# mini.net
KiCad netlist of a schematic drawn in EAGLE
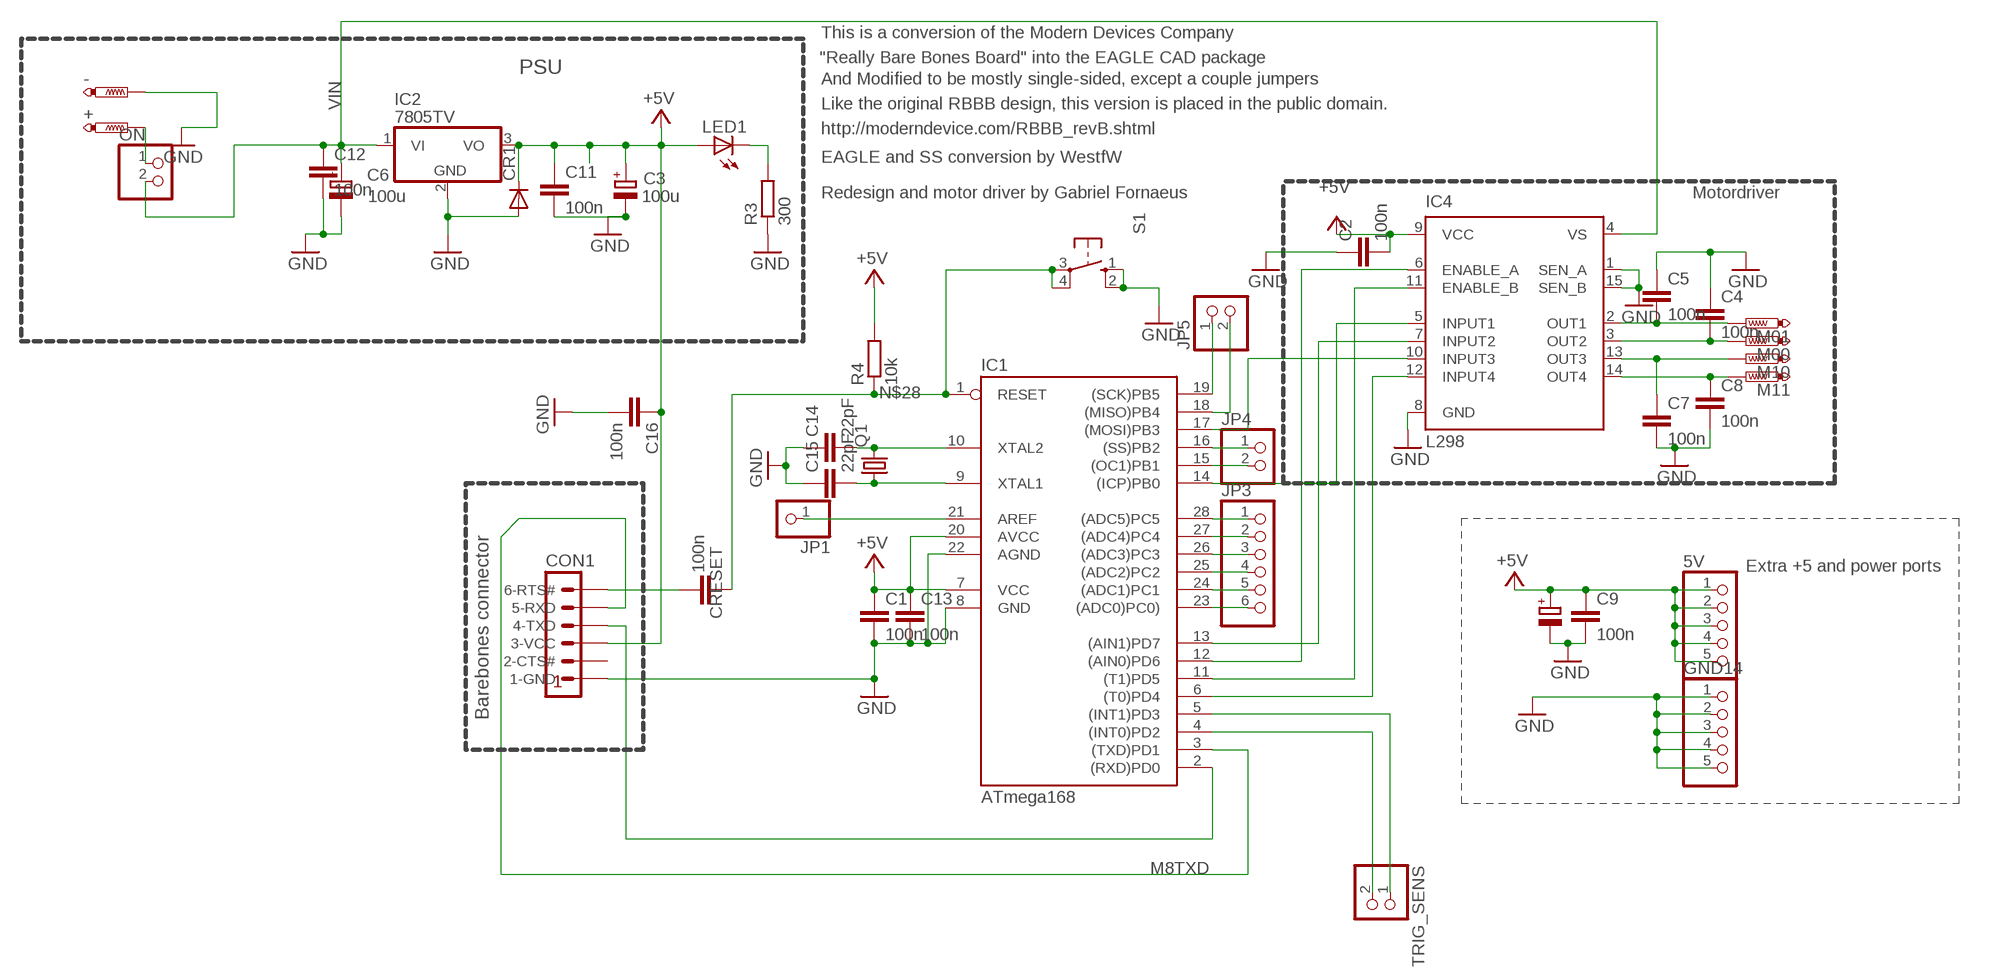
[diagram p0: schematic, sheet 1]

(export (version "E")
  (design (tool "Eeschema 10.0.6"))
  (components
    (comp (ref "+")
      (value "PTR1PAD1-13Y")
      (footprint "eagle-import:P1-13Y")
      (libsource (lib "eagle-import") (part "PTR1PAD1-13Y"))
    )
    (comp (ref "-")
      (value "PTR1PAD1-13Y")
      (footprint "eagle-import:P1-13Y")
      (libsource (lib "eagle-import") (part "PTR1PAD1-13Y"))
    )
    (comp (ref "5V")
      (value "PINHD-1X5")
      (footprint "eagle-import:1X05")
      (libsource (lib "eagle-import") (part "PINHD-1X5"))
    )
    (comp (ref "C1")
      (value "100n")
      (footprint "eagle-import:C025-025X050")
      (libsource (lib "eagle-import") (part "C-EU025-025X050"))
    )
    (comp (ref "C2")
      (value "100n")
      (footprint "eagle-import:C025-025X050")
      (libsource (lib "eagle-import") (part "C-EU025-025X050"))
    )
    (comp (ref "C3")
      (value "100u")
      (footprint "eagle-import:E2,5-7")
      (libsource (lib "eagle-import") (part "CPOL-EUE2.5-7"))
    )
    (comp (ref "C4")
      (value "100n")
      (footprint "eagle-import:C025-025X050")
      (libsource (lib "eagle-import") (part "C-EU025-025X050"))
    )
    (comp (ref "C5")
      (value "100n")
      (footprint "eagle-import:C025-025X050")
      (libsource (lib "eagle-import") (part "C-EU025-025X050"))
    )
    (comp (ref "C6")
      (value "100u")
      (footprint "eagle-import:E2,5-7")
      (libsource (lib "eagle-import") (part "CPOL-EUE2.5-7"))
    )
    (comp (ref "C7")
      (value "100n")
      (footprint "eagle-import:C025-025X050")
      (libsource (lib "eagle-import") (part "C-EU025-025X050"))
    )
    (comp (ref "C8")
      (value "100n")
      (footprint "eagle-import:C025-025X050")
      (libsource (lib "eagle-import") (part "C-EU025-025X050"))
    )
    (comp (ref "C9")
      (value "100n")
      (footprint "eagle-import:C025-025X050")
      (libsource (lib "eagle-import") (part "C-EU025-025X050"))
    )
    (comp (ref "C10")
      (value "100u")
      (footprint "eagle-import:E2,5-7")
      (libsource (lib "eagle-import") (part "CPOL-EUE2.5-7"))
    )
    (comp (ref "C11")
      (value "100n")
      (footprint "eagle-import:C025-025X050")
      (libsource (lib "eagle-import") (part "C-EU025-025X050"))
    )
    (comp (ref "C12")
      (value "100n")
      (footprint "eagle-import:C025-025X050")
      (libsource (lib "eagle-import") (part "C-EU025-025X050"))
    )
    (comp (ref "C13")
      (value "100n")
      (footprint "eagle-import:C025-025X050")
      (libsource (lib "eagle-import") (part "C-EU025-025X050"))
    )
    (comp (ref "C14")
      (value "22pF")
      (footprint "eagle-import:C025-024X044")
      (libsource (lib "eagle-import") (part "resistor_C-EU025-024X044"))
    )
    (comp (ref "C15")
      (value "22pF")
      (footprint "eagle-import:C025-024X044")
      (libsource (lib "eagle-import") (part "resistor_C-EU025-024X044"))
    )
    (comp (ref "C16")
      (value "100n")
      (footprint "eagle-import:C025-025X050")
      (libsource (lib "eagle-import") (part "C-EU025-025X050"))
    )
    (comp (ref "CON1")
      (value "FTDI-TTL232R")
      (footprint "eagle-import:MA06-1")
      (libsource (lib "eagle-import") (part "FTDI-TTL232R"))
    )
    (comp (ref "CR1")
      (value "DIODE-1ARECT-2V")
      (footprint "eagle-import:DO41-2V")
      (libsource (lib "eagle-import") (part "DIODE-1ARECT-2V"))
    )
    (comp (ref "CRESET")
      (value "100n")
      (footprint "eagle-import:C025-025X050")
      (libsource (lib "eagle-import") (part "C-EU025-025X050"))
    )
    (comp (ref "GND14")
      (value "PINHD-1X5")
      (footprint "eagle-import:1X05")
      (libsource (lib "eagle-import") (part "PINHD-1X5"))
    )
    (comp (ref "IC1")
      (value "ATmega168")
      (footprint "eagle-import:DIL28-3")
      (libsource (lib "eagle-import") (part "AT90S4433P"))
    )
    (comp (ref "IC2")
      (value "7805TV")
      (footprint "eagle-import:TO220V")
      (libsource (lib "eagle-import") (part "78TV05"))
    )
    (comp (ref "IC4")
      (value "L298")
      (footprint "eagle-import:MULTIWATT-15")
      (fields (field (name "MPN") "L298N"))
      (libsource (lib "eagle-import") (part "L298"))
    )
    (comp (ref "JP1")
      (value "PINHD-1X1")
      (footprint "eagle-import:1X01")
      (libsource (lib "eagle-import") (part "PINHD-1X1"))
    )
    (comp (ref "JP3")
      (value "PINHD-1X6")
      (footprint "eagle-import:1X06")
      (libsource (lib "eagle-import") (part "PINHD-1X6"))
    )
    (comp (ref "JP4")
      (value "PINHD-1X2")
      (footprint "eagle-import:1X02")
      (libsource (lib "eagle-import") (part "PINHD-1X2"))
    )
    (comp (ref "JP5")
      (value "PINHD-1X2")
      (footprint "eagle-import:1X02")
      (libsource (lib "eagle-import") (part "PINHD-1X2"))
    )
    (comp (ref "LED1")
      (value "LED3MM")
      (footprint "eagle-import:LED3MM")
      (libsource (lib "eagle-import") (part "LED3MM"))
    )
    (comp (ref "M00")
      (value "PTR1PAD1-13Y")
      (footprint "eagle-import:P1-13Y")
      (libsource (lib "eagle-import") (part "PTR1PAD1-13Y"))
    )
    (comp (ref "M01")
      (value "PTR1PAD1-13Y")
      (footprint "eagle-import:P1-13Y")
      (libsource (lib "eagle-import") (part "PTR1PAD1-13Y"))
    )
    (comp (ref "M10")
      (value "PTR1PAD1-13Y")
      (footprint "eagle-import:P1-13Y")
      (libsource (lib "eagle-import") (part "PTR1PAD1-13Y"))
    )
    (comp (ref "M11")
      (value "PTR1PAD1-13Y")
      (footprint "eagle-import:P1-13Y")
      (libsource (lib "eagle-import") (part "PTR1PAD1-13Y"))
    )
    (comp (ref "ON")
      (value "PINHD-1X2")
      (footprint "eagle-import:1X02")
      (libsource (lib "eagle-import") (part "PINHD-1X2"))
    )
    (comp (ref "Q1")
      (value "CRYSTALHC49S")
      (footprint "eagle-import:HC49_S")
      (libsource (lib "eagle-import") (part "CRYSTALHC49S"))
    )
    (comp (ref "R3")
      (value "300")
      (footprint "eagle-import:0204_7")
      (libsource (lib "eagle-import") (part "R-EU_0204/7"))
    )
    (comp (ref "R4")
      (value "10k")
      (footprint "eagle-import:0204_7")
      (libsource (lib "eagle-import") (part "R-EU_0204/7"))
    )
    (comp (ref "S1")
      (value "10-XX")
      (footprint "eagle-import:B3F-10XX")
      (libsource (lib "eagle-import") (part "10-XX"))
    )
    (comp (ref "TRIG_SENS")
      (value "PINHD-1X2")
      (footprint "eagle-import:1X02")
      (libsource (lib "eagle-import") (part "PINHD-1X2"))
    )
  )
  (nets
    (net (code "1") (name "+5V") (class "Default")
      (node (ref "5V") (pin "1") (pinfunction "1_1") (pintype "passive"))
      (node (ref "5V") (pin "2") (pinfunction "2_2") (pintype "passive"))
      (node (ref "5V") (pin "3") (pinfunction "3_3") (pintype "passive"))
      (node (ref "5V") (pin "4") (pinfunction "4_4") (pintype "passive"))
      (node (ref "5V") (pin "5") (pinfunction "5_5") (pintype "passive"))
      (node (ref "C1") (pin "1") (pinfunction "1_1") (pintype "passive"))
      (node (ref "C10") (pin "+") (pinfunction "+_+") (pintype "passive"))
      (node (ref "C11") (pin "1") (pinfunction "1_1") (pintype "passive"))
      (node (ref "C13") (pin "1") (pinfunction "1_1") (pintype "passive"))
      (node (ref "C16") (pin "1") (pinfunction "1_1") (pintype "passive"))
      (node (ref "C2") (pin "2") (pinfunction "2_2") (pintype "passive"))
      (node (ref "C3") (pin "+") (pinfunction "+_+") (pintype "passive"))
      (node (ref "C9") (pin "1") (pinfunction "1_1") (pintype "passive"))
      (node (ref "CON1") (pin "3") (pinfunction "3-VCC_3") (pintype "passive"))
      (node (ref "CR1") (pin "C") (pinfunction "C_C") (pintype "passive"))
      (node (ref "IC1") (pin "20") (pinfunction "AVCC_20") (pintype "power_in"))
      (node (ref "IC1") (pin "7") (pinfunction "VCC_7") (pintype "power_in"))
      (node (ref "IC2") (pin "3") (pinfunction "VO_3") (pintype "passive"))
      (node (ref "IC4") (pin "9") (pinfunction "VCC_9") (pintype "power_in"))
      (node (ref "LED1") (pin "A") (pinfunction "A_A") (pintype "passive"))
      (node (ref "R4") (pin "2") (pinfunction "2_2") (pintype "passive"))
    )
    (net (code "2") (name "/M8TXD") (class "Default")
      (node (ref "CON1") (pin "5") (pinfunction "5-RXD_5") (pintype "passive"))
      (node (ref "IC1") (pin "3") (pinfunction "(TXD)PD1_3") (pintype "bidirectional"))
    )
    (net (code "3") (name "/N$28") (class "Default")
      (node (ref "CRESET") (pin "2") (pinfunction "2_2") (pintype "passive"))
      (node (ref "IC1") (pin "1") (pinfunction "RESET_1") (pintype "input"))
      (node (ref "R4") (pin "1") (pinfunction "1_1") (pintype "passive"))
      (node (ref "S1") (pin "3") (pinfunction "P_3") (pintype "passive"))
      (node (ref "S1") (pin "4") (pinfunction "P1_4") (pintype "passive"))
    )
    (net (code "4") (name "/VIN") (class "Default")
      (node (ref "C12") (pin "1") (pinfunction "1_1") (pintype "passive"))
      (node (ref "C6") (pin "+") (pinfunction "+_+") (pintype "passive"))
      (node (ref "IC2") (pin "1") (pinfunction "VI_1") (pintype "input"))
      (node (ref "IC4") (pin "4") (pinfunction "VS_4") (pintype "power_in"))
      (node (ref "ON") (pin "2") (pinfunction "2_2") (pintype "passive"))
    )
    (net (code "5") (name "GND") (class "Default")
      (node (ref "-") (pin "TP") (pinfunction "TP_TP") (pintype "input"))
      (node (ref "C1") (pin "2") (pinfunction "2_2") (pintype "passive"))
      (node (ref "C10") (pin "-") (pinfunction "-_-") (pintype "passive"))
      (node (ref "C11") (pin "2") (pinfunction "2_2") (pintype "passive"))
      (node (ref "C12") (pin "2") (pinfunction "2_2") (pintype "passive"))
      (node (ref "C13") (pin "2") (pinfunction "2_2") (pintype "passive"))
      (node (ref "C14") (pin "1") (pinfunction "1_1") (pintype "passive"))
      (node (ref "C15") (pin "1") (pinfunction "1_1") (pintype "passive"))
      (node (ref "C16") (pin "2") (pinfunction "2_2") (pintype "passive"))
      (node (ref "C2") (pin "1") (pinfunction "1_1") (pintype "passive"))
      (node (ref "C3") (pin "-") (pinfunction "-_-") (pintype "passive"))
      (node (ref "C4") (pin "1") (pinfunction "1_1") (pintype "passive"))
      (node (ref "C5") (pin "1") (pinfunction "1_1") (pintype "passive"))
      (node (ref "C6") (pin "-") (pinfunction "-_-") (pintype "passive"))
      (node (ref "C7") (pin "2") (pinfunction "2_2") (pintype "passive"))
      (node (ref "C8") (pin "2") (pinfunction "2_2") (pintype "passive"))
      (node (ref "C9") (pin "2") (pinfunction "2_2") (pintype "passive"))
      (node (ref "CON1") (pin "1") (pinfunction "1-GND_1") (pintype "passive"))
      (node (ref "CR1") (pin "A") (pinfunction "A_A") (pintype "passive"))
      (node (ref "GND14") (pin "1") (pinfunction "1_1") (pintype "passive"))
      (node (ref "GND14") (pin "2") (pinfunction "2_2") (pintype "passive"))
      (node (ref "GND14") (pin "3") (pinfunction "3_3") (pintype "passive"))
      (node (ref "GND14") (pin "4") (pinfunction "4_4") (pintype "passive"))
      (node (ref "GND14") (pin "5") (pinfunction "5_5") (pintype "passive"))
      (node (ref "IC1") (pin "22") (pinfunction "AGND_22") (pintype "power_in"))
      (node (ref "IC1") (pin "8") (pinfunction "GND_8") (pintype "power_in"))
      (node (ref "IC2") (pin "2") (pinfunction "GND_2") (pintype "passive"))
      (node (ref "IC4") (pin "1") (pinfunction "SEN_A_1") (pintype "input"))
      (node (ref "IC4") (pin "15") (pinfunction "SEN_B_15") (pintype "input"))
      (node (ref "IC4") (pin "8") (pinfunction "GND_8") (pintype "power_in"))
      (node (ref "R3") (pin "1") (pinfunction "1_1") (pintype "passive"))
      (node (ref "S1") (pin "1") (pinfunction "S_1") (pintype "passive"))
      (node (ref "S1") (pin "2") (pinfunction "S1_2") (pintype "passive"))
    )
    (net (code "6") (name "Net-(+-PadTP)") (class "Default")
      (node (ref "+") (pin "TP") (pinfunction "TP_TP") (pintype "input"))
      (node (ref "ON") (pin "1") (pinfunction "1_1") (pintype "passive"))
    )
    (net (code "7") (name "Net-(CON1-4-TXD)") (class "Default")
      (node (ref "CON1") (pin "4") (pinfunction "4-TXD_4") (pintype "passive"))
      (node (ref "IC1") (pin "2") (pinfunction "(RXD)PD0_2") (pintype "bidirectional"))
    )
    (net (code "8") (name "Net-(CON1-6-RTS#)") (class "Default")
      (node (ref "CON1") (pin "6") (pinfunction "6-RTS#_6") (pintype "passive"))
      (node (ref "CRESET") (pin "1") (pinfunction "1_1") (pintype "passive"))
    )
    (net (code "9") (name "Net-(IC1-(ADC0)PC0))") (class "Default")
      (node (ref "IC1") (pin "23") (pinfunction "(ADC0)PC0)_23") (pintype "bidirectional"))
      (node (ref "JP3") (pin "6") (pinfunction "6_6") (pintype "passive"))
    )
    (net (code "10") (name "Net-(IC1-(ADC1)PC1)") (class "Default")
      (node (ref "IC1") (pin "24") (pinfunction "(ADC1)PC1_24") (pintype "bidirectional"))
      (node (ref "JP3") (pin "5") (pinfunction "5_5") (pintype "passive"))
    )
    (net (code "11") (name "Net-(IC1-(ADC2)PC2)") (class "Default")
      (node (ref "IC1") (pin "25") (pinfunction "(ADC2)PC2_25") (pintype "bidirectional"))
      (node (ref "JP3") (pin "4") (pinfunction "4_4") (pintype "passive"))
    )
    (net (code "12") (name "Net-(IC1-(ADC3)PC3)") (class "Default")
      (node (ref "IC1") (pin "26") (pinfunction "(ADC3)PC3_26") (pintype "bidirectional"))
      (node (ref "JP3") (pin "3") (pinfunction "3_3") (pintype "passive"))
    )
    (net (code "13") (name "Net-(IC1-(ADC4)PC4)") (class "Default")
      (node (ref "IC1") (pin "27") (pinfunction "(ADC4)PC4_27") (pintype "bidirectional"))
      (node (ref "JP3") (pin "2") (pinfunction "2_2") (pintype "passive"))
    )
    (net (code "14") (name "Net-(IC1-(ADC5)PC5)") (class "Default")
      (node (ref "IC1") (pin "28") (pinfunction "(ADC5)PC5_28") (pintype "bidirectional"))
      (node (ref "JP3") (pin "1") (pinfunction "1_1") (pintype "passive"))
    )
    (net (code "15") (name "Net-(IC1-(AIN0)PD6)") (class "Default")
      (node (ref "IC1") (pin "12") (pinfunction "(AIN0)PD6_12") (pintype "bidirectional"))
      (node (ref "IC4") (pin "6") (pinfunction "ENABLE_A_6") (pintype "input"))
    )
    (net (code "16") (name "Net-(IC1-(AIN1)PD7)") (class "Default")
      (node (ref "IC1") (pin "13") (pinfunction "(AIN1)PD7_13") (pintype "bidirectional"))
      (node (ref "IC4") (pin "7") (pinfunction "INPUT2_7") (pintype "input"))
    )
    (net (code "17") (name "Net-(IC1-(ICP)PB0)") (class "Default")
      (node (ref "IC1") (pin "14") (pinfunction "(ICP)PB0_14") (pintype "bidirectional"))
      (node (ref "IC4") (pin "5") (pinfunction "INPUT1_5") (pintype "input"))
    )
    (net (code "18") (name "Net-(IC1-(INT0)PD2)") (class "Default")
      (node (ref "IC1") (pin "4") (pinfunction "(INT0)PD2_4") (pintype "bidirectional"))
      (node (ref "TRIG_SENS") (pin "2") (pinfunction "2_2") (pintype "passive"))
    )
    (net (code "19") (name "Net-(IC1-(INT1)PD3)") (class "Default")
      (node (ref "IC1") (pin "5") (pinfunction "(INT1)PD3_5") (pintype "bidirectional"))
      (node (ref "TRIG_SENS") (pin "1") (pinfunction "1_1") (pintype "passive"))
    )
    (net (code "20") (name "Net-(IC1-(MISO)PB4)") (class "Default")
      (node (ref "IC1") (pin "18") (pinfunction "(MISO)PB4_18") (pintype "bidirectional"))
      (node (ref "JP5") (pin "2") (pinfunction "2_2") (pintype "passive"))
    )
    (net (code "21") (name "Net-(IC1-(MOSI)PB3)") (class "Default")
      (node (ref "IC1") (pin "17") (pinfunction "(MOSI)PB3_17") (pintype "bidirectional"))
      (node (ref "IC4") (pin "10") (pinfunction "INPUT3_10") (pintype "input"))
    )
    (net (code "22") (name "Net-(IC1-(OC1)PB1)") (class "Default")
      (node (ref "IC1") (pin "15") (pinfunction "(OC1)PB1_15") (pintype "bidirectional"))
      (node (ref "JP4") (pin "2") (pinfunction "2_2") (pintype "passive"))
    )
    (net (code "23") (name "Net-(IC1-(SCK)PB5)") (class "Default")
      (node (ref "IC1") (pin "19") (pinfunction "(SCK)PB5_19") (pintype "bidirectional"))
      (node (ref "JP5") (pin "1") (pinfunction "1_1") (pintype "passive"))
    )
    (net (code "24") (name "Net-(IC1-(SS)PB2)") (class "Default")
      (node (ref "IC1") (pin "16") (pinfunction "(SS)PB2_16") (pintype "bidirectional"))
      (node (ref "JP4") (pin "1") (pinfunction "1_1") (pintype "passive"))
    )
    (net (code "25") (name "Net-(IC1-(T0)PD4)") (class "Default")
      (node (ref "IC1") (pin "6") (pinfunction "(T0)PD4_6") (pintype "bidirectional"))
      (node (ref "IC4") (pin "12") (pinfunction "INPUT4_12") (pintype "input"))
    )
    (net (code "26") (name "Net-(IC1-(T1)PD5)") (class "Default")
      (node (ref "IC1") (pin "11") (pinfunction "(T1)PD5_11") (pintype "bidirectional"))
      (node (ref "IC4") (pin "11") (pinfunction "ENABLE_B_11") (pintype "input"))
    )
    (net (code "27") (name "Net-(IC1-AREF)") (class "Default")
      (node (ref "IC1") (pin "21") (pinfunction "AREF_21") (pintype "passive"))
      (node (ref "JP1") (pin "1") (pinfunction "1_1") (pintype "passive"))
    )
    (net (code "28") (name "Net-(IC1-XTAL1)") (class "Default")
      (node (ref "C15") (pin "2") (pinfunction "2_2") (pintype "passive"))
      (node (ref "IC1") (pin "9") (pinfunction "XTAL1_9") (pintype "bidirectional"))
      (node (ref "Q1") (pin "1") (pinfunction "1_1") (pintype "passive"))
    )
    (net (code "29") (name "Net-(IC1-XTAL2)") (class "Default")
      (node (ref "C14") (pin "2") (pinfunction "2_2") (pintype "passive"))
      (node (ref "IC1") (pin "10") (pinfunction "XTAL2_10") (pintype "bidirectional"))
      (node (ref "Q1") (pin "2") (pinfunction "2_2") (pintype "passive"))
    )
    (net (code "30") (name "Net-(IC4-OUT1)") (class "Default")
      (node (ref "C5") (pin "2") (pinfunction "2_2") (pintype "passive"))
      (node (ref "IC4") (pin "2") (pinfunction "OUT1_2") (pintype "output"))
      (node (ref "M01") (pin "TP") (pinfunction "TP_TP") (pintype "input"))
    )
    (net (code "31") (name "Net-(IC4-OUT2)") (class "Default")
      (node (ref "C4") (pin "2") (pinfunction "2_2") (pintype "passive"))
      (node (ref "IC4") (pin "3") (pinfunction "OUT2_3") (pintype "output"))
      (node (ref "M00") (pin "TP") (pinfunction "TP_TP") (pintype "input"))
    )
    (net (code "32") (name "Net-(IC4-OUT3)") (class "Default")
      (node (ref "C7") (pin "1") (pinfunction "1_1") (pintype "passive"))
      (node (ref "IC4") (pin "13") (pinfunction "OUT3_13") (pintype "output"))
      (node (ref "M10") (pin "TP") (pinfunction "TP_TP") (pintype "input"))
    )
    (net (code "33") (name "Net-(IC4-OUT4)") (class "Default")
      (node (ref "C8") (pin "1") (pinfunction "1_1") (pintype "passive"))
      (node (ref "IC4") (pin "14") (pinfunction "OUT4_14") (pintype "output"))
      (node (ref "M11") (pin "TP") (pinfunction "TP_TP") (pintype "input"))
    )
    (net (code "34") (name "Net-(LED1-C)") (class "Default")
      (node (ref "LED1") (pin "K") (pinfunction "C_K") (pintype "passive"))
      (node (ref "R3") (pin "2") (pinfunction "2_2") (pintype "passive"))
    )
    (net (code "35") (name "unconnected-(CON1-2-CTS#-Pad2)") (class "Default")
      (node (ref "CON1") (pin "2") (pinfunction "2-CTS#_2") (pintype "passive"))
    )
  )
)
